# base.net
KiCad netlist of a schematic drawn in EAGLE
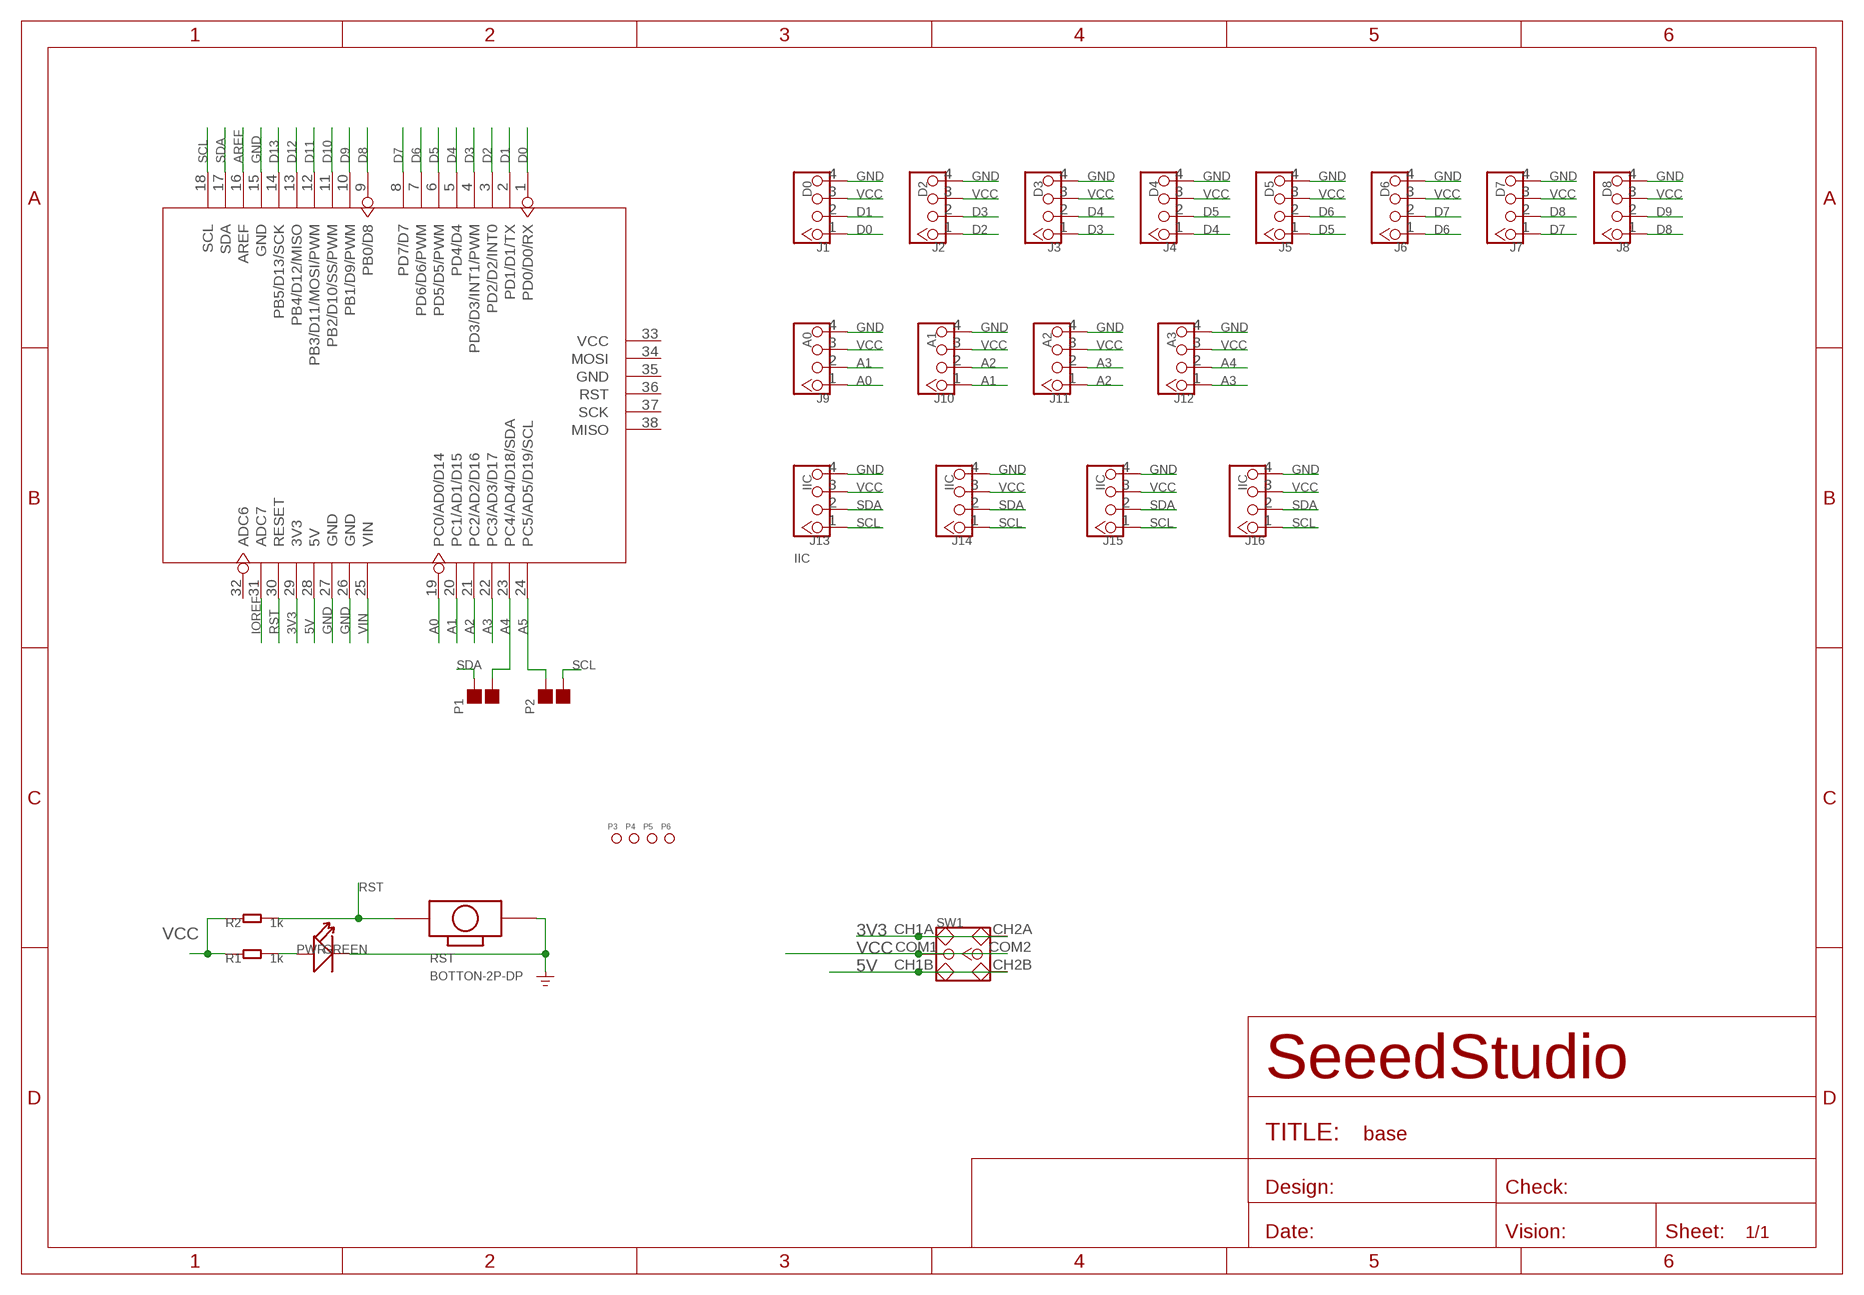
[diagram p0: schematic, sheet 1]

(export (version "E")
  (design (tool "Eeschema 10.0.6"))
  (components
    (comp (ref "J1")
      (value "D0")
      (footprint "eagle-import:4P-2.0")
      (libsource (lib "eagle-import") (part "TWIG-4P-2.0-2.0"))
    )
    (comp (ref "J2")
      (value "D2")
      (footprint "eagle-import:4P-2.0")
      (libsource (lib "eagle-import") (part "TWIG-4P-2.0-2.0"))
    )
    (comp (ref "J3")
      (value "D3")
      (footprint "eagle-import:4P-2.0")
      (libsource (lib "eagle-import") (part "TWIG-4P-2.0-2.0"))
    )
    (comp (ref "J4")
      (value "D4")
      (footprint "eagle-import:4P-2.0")
      (libsource (lib "eagle-import") (part "TWIG-4P-2.0-2.0"))
    )
    (comp (ref "J5")
      (value "D5")
      (footprint "eagle-import:4P-2.0")
      (libsource (lib "eagle-import") (part "TWIG-4P-2.0-2.0"))
    )
    (comp (ref "J6")
      (value "D6")
      (footprint "eagle-import:4P-2.0")
      (libsource (lib "eagle-import") (part "TWIG-4P-2.0-2.0"))
    )
    (comp (ref "J7")
      (value "D7")
      (footprint "eagle-import:4P-2.0")
      (libsource (lib "eagle-import") (part "TWIG-4P-2.0-2.0"))
    )
    (comp (ref "J8")
      (value "D8")
      (footprint "eagle-import:4P-2.0")
      (libsource (lib "eagle-import") (part "TWIG-4P-2.0-2.0"))
    )
    (comp (ref "J9")
      (value "A0")
      (footprint "eagle-import:4P-2.0-90D")
      (libsource (lib "eagle-import") (part "TWIG-4P-2.0'90D'"))
    )
    (comp (ref "J10")
      (value "A1")
      (footprint "eagle-import:4P-2.0-90D")
      (libsource (lib "eagle-import") (part "TWIG-4P-2.0'90D'"))
    )
    (comp (ref "J11")
      (value "A2")
      (footprint "eagle-import:4P-2.0-90D")
      (libsource (lib "eagle-import") (part "TWIG-4P-2.0'90D'"))
    )
    (comp (ref "J12")
      (value "A3")
      (footprint "eagle-import:4P-2.0-90D")
      (libsource (lib "eagle-import") (part "TWIG-4P-2.0'90D'"))
    )
    (comp (ref "J13")
      (value "IIC")
      (footprint "eagle-import:4P-2.0")
      (libsource (lib "eagle-import") (part "TWIG-4P-2.0-2.0"))
    )
    (comp (ref "J14")
      (value "IIC")
      (footprint "eagle-import:4P-2.0")
      (libsource (lib "eagle-import") (part "TWIG-4P-2.0-2.0"))
    )
    (comp (ref "J15")
      (value "IIC")
      (footprint "eagle-import:4P-2.0")
      (libsource (lib "eagle-import") (part "TWIG-4P-2.0-2.0"))
    )
    (comp (ref "J16")
      (value "IIC")
      (footprint "eagle-import:4P-2.0")
      (libsource (lib "eagle-import") (part "TWIG-4P-2.0-2.0"))
    )
    (comp (ref "P1")
      (value "DNP")
      (footprint "eagle-import:2P-SMD-1.78X1.27")
      (libsource (lib "eagle-import") (part "PAD-JUMPER-2P"))
    )
    (comp (ref "P2")
      (value "DNP")
      (footprint "eagle-import:2P-SMD-1.78X1.27")
      (libsource (lib "eagle-import") (part "PAD-JUMPER-2P"))
    )
    (comp (ref "P3")
      (value "PAD-MARK")
      (footprint "eagle-import:ROUND-MARK-1.0")
      (fields (field (name "PARTNO") "DNP"))
      (libsource (lib "eagle-import") (part "PAD-MARK"))
    )
    (comp (ref "P4")
      (value "PAD-MARK")
      (footprint "eagle-import:ROUND-MARK-1.0")
      (fields (field (name "PARTNO") "DNP"))
      (libsource (lib "eagle-import") (part "PAD-MARK"))
    )
    (comp (ref "P5")
      (value "PAD-MARK")
      (footprint "eagle-import:ROUND-MARK-1.0")
      (fields (field (name "PARTNO") "DNP"))
      (libsource (lib "eagle-import") (part "PAD-MARK"))
    )
    (comp (ref "P6")
      (value "PAD-MARK")
      (footprint "eagle-import:ROUND-MARK-1.0")
      (fields (field (name "PARTNO") "DNP"))
      (libsource (lib "eagle-import") (part "PAD-MARK"))
    )
    (comp (ref "PWR")
      (value "GREEN")
      (footprint "eagle-import:LED-2P-2.54-3MM")
      (libsource (lib "eagle-import") (part "LED-3MM"))
    )
    (comp (ref "R1")
      (value "1k")
      (footprint "eagle-import:R0603")
      (libsource (lib "eagle-import") (part "R-0603"))
    )
    (comp (ref "R2")
      (value "1k")
      (footprint "eagle-import:R0603")
      (libsource (lib "eagle-import") (part "R-0603"))
    )
    (comp (ref "RST")
      (value "BOTTON-2P-DP")
      (footprint "eagle-import:2P-7.62X3.56-90D")
      (libsource (lib "eagle-import") (part "BOTTON-2P-90"))
    )
    (comp (ref "SW1")
      (value "SWITCH-2CH-6P'90D'")
      (footprint "eagle-import:6P-2CH-2.5-9.1X3.5X3.2H-90D")
      (libsource (lib "eagle-import") (part "SWITCH-2CH-6P'90D'"))
    )
    (comp (ref "U2")
      (value "DIP Long Blue Female Header")
      (footprint "eagle-import:ARDUINO-38P")
      (libsource (lib "eagle-import") (part "ARDUINO-38P"))
    )
  )
  (nets
    (net (code "1") (name "/3V3") (class "Default")
      (node (ref "SW1") (pin "CH1A") (pinfunction "CH1A_CH1A") (pintype "bidirectional"))
      (node (ref "SW1") (pin "CH2A") (pinfunction "CH2A_CH2A") (pintype "bidirectional"))
      (node (ref "U2") (pin "29") (pinfunction "3V3_29") (pintype "bidirectional"))
    )
    (net (code "2") (name "/5V") (class "Default")
      (node (ref "SW1") (pin "CH1B") (pinfunction "CH1B_CH1B") (pintype "bidirectional"))
      (node (ref "SW1") (pin "CH2B") (pinfunction "CH2B_CH2B") (pintype "bidirectional"))
      (node (ref "U2") (pin "28") (pinfunction "5V_28") (pintype "bidirectional"))
    )
    (net (code "3") (name "/A0") (class "Default")
      (node (ref "J9") (pin "1") (pinfunction "1_1") (pintype "bidirectional"))
      (node (ref "U2") (pin "19") (pinfunction "PC0/AD0/D14_19") (pintype "bidirectional"))
    )
    (net (code "4") (name "/A1") (class "Default")
      (node (ref "J10") (pin "1") (pinfunction "1_1") (pintype "bidirectional"))
      (node (ref "J9") (pin "2") (pinfunction "2_2") (pintype "bidirectional"))
      (node (ref "U2") (pin "20") (pinfunction "PC1/AD1/D15_20") (pintype "bidirectional"))
    )
    (net (code "5") (name "/A2") (class "Default")
      (node (ref "J10") (pin "2") (pinfunction "2_2") (pintype "bidirectional"))
      (node (ref "J11") (pin "1") (pinfunction "1_1") (pintype "bidirectional"))
      (node (ref "U2") (pin "21") (pinfunction "PC2/AD2/D16_21") (pintype "bidirectional"))
    )
    (net (code "6") (name "/A3") (class "Default")
      (node (ref "J11") (pin "2") (pinfunction "2_2") (pintype "bidirectional"))
      (node (ref "J12") (pin "1") (pinfunction "1_1") (pintype "bidirectional"))
      (node (ref "U2") (pin "22") (pinfunction "PC3/AD3/D17_22") (pintype "bidirectional"))
    )
    (net (code "7") (name "/A4") (class "Default")
      (node (ref "J12") (pin "2") (pinfunction "2_2") (pintype "bidirectional"))
      (node (ref "P1") (pin "1") (pinfunction "1_1") (pintype "bidirectional"))
      (node (ref "U2") (pin "23") (pinfunction "PC4/AD4/D18/SDA_23") (pintype "bidirectional"))
    )
    (net (code "8") (name "/A5") (class "Default")
      (node (ref "P2") (pin "2") (pinfunction "2_2") (pintype "bidirectional"))
      (node (ref "U2") (pin "24") (pinfunction "PC5/AD5/D19/SCL_24") (pintype "bidirectional"))
    )
    (net (code "9") (name "/AREF") (class "Default")
      (node (ref "U2") (pin "16") (pinfunction "AREF_16") (pintype "bidirectional"))
    )
    (net (code "10") (name "/D0") (class "Default")
      (node (ref "J1") (pin "1") (pinfunction "1_1") (pintype "bidirectional"))
      (node (ref "U2") (pin "1") (pinfunction "PD0/D0/RX_1") (pintype "bidirectional"))
    )
    (net (code "11") (name "/D1") (class "Default")
      (node (ref "J1") (pin "2") (pinfunction "2_2") (pintype "bidirectional"))
      (node (ref "U2") (pin "2") (pinfunction "PD1/D1/TX_2") (pintype "bidirectional"))
    )
    (net (code "12") (name "/D2") (class "Default")
      (node (ref "J2") (pin "1") (pinfunction "1_1") (pintype "bidirectional"))
      (node (ref "U2") (pin "3") (pinfunction "PD2/D2/INT0_3") (pintype "bidirectional"))
    )
    (net (code "13") (name "/D3") (class "Default")
      (node (ref "J2") (pin "2") (pinfunction "2_2") (pintype "bidirectional"))
      (node (ref "J3") (pin "1") (pinfunction "1_1") (pintype "bidirectional"))
      (node (ref "U2") (pin "4") (pinfunction "PD3/D3/INT1/PWM_4") (pintype "bidirectional"))
    )
    (net (code "14") (name "/D4") (class "Default")
      (node (ref "J3") (pin "2") (pinfunction "2_2") (pintype "bidirectional"))
      (node (ref "J4") (pin "1") (pinfunction "1_1") (pintype "bidirectional"))
      (node (ref "U2") (pin "5") (pinfunction "PD4/D4_5") (pintype "bidirectional"))
    )
    (net (code "15") (name "/D5") (class "Default")
      (node (ref "J4") (pin "2") (pinfunction "2_2") (pintype "bidirectional"))
      (node (ref "J5") (pin "1") (pinfunction "1_1") (pintype "bidirectional"))
      (node (ref "U2") (pin "6") (pinfunction "PD5/D5/PWM_6") (pintype "bidirectional"))
    )
    (net (code "16") (name "/D6") (class "Default")
      (node (ref "J5") (pin "2") (pinfunction "2_2") (pintype "bidirectional"))
      (node (ref "J6") (pin "1") (pinfunction "1_1") (pintype "bidirectional"))
      (node (ref "U2") (pin "7") (pinfunction "PD6/D6/PWM_7") (pintype "bidirectional"))
    )
    (net (code "17") (name "/D7") (class "Default")
      (node (ref "J6") (pin "2") (pinfunction "2_2") (pintype "bidirectional"))
      (node (ref "J7") (pin "1") (pinfunction "1_1") (pintype "bidirectional"))
      (node (ref "U2") (pin "8") (pinfunction "PD7/D7_8") (pintype "bidirectional"))
    )
    (net (code "18") (name "/D8") (class "Default")
      (node (ref "J7") (pin "2") (pinfunction "2_2") (pintype "bidirectional"))
      (node (ref "J8") (pin "1") (pinfunction "1_1") (pintype "bidirectional"))
      (node (ref "U2") (pin "9") (pinfunction "PB0/D8_9") (pintype "bidirectional"))
    )
    (net (code "19") (name "/D9") (class "Default")
      (node (ref "J8") (pin "2") (pinfunction "2_2") (pintype "bidirectional"))
      (node (ref "U2") (pin "10") (pinfunction "PB1/D9/PWM_10") (pintype "bidirectional"))
    )
    (net (code "20") (name "/D10") (class "Default")
      (node (ref "U2") (pin "11") (pinfunction "PB2/D10/SS/PWM_11") (pintype "bidirectional"))
    )
    (net (code "21") (name "/D11") (class "Default")
      (node (ref "U2") (pin "12") (pinfunction "PB3/D11/MOSI/PWM_12") (pintype "bidirectional"))
    )
    (net (code "22") (name "/D12") (class "Default")
      (node (ref "U2") (pin "13") (pinfunction "PB4/D12/MISO_13") (pintype "bidirectional"))
    )
    (net (code "23") (name "/D13") (class "Default")
      (node (ref "U2") (pin "14") (pinfunction "PB5/D13/SCK_14") (pintype "bidirectional"))
    )
    (net (code "24") (name "/IOREF") (class "Default")
      (node (ref "U2") (pin "31") (pinfunction "ADC7_31") (pintype "bidirectional"))
    )
    (net (code "25") (name "/RST") (class "Default")
      (node (ref "R2") (pin "2") (pinfunction "2_2") (pintype "passive"))
      (node (ref "RST") (pin "P$1") (pinfunction "1_P$1") (pintype "bidirectional"))
      (node (ref "U2") (pin "30") (pinfunction "RESET_30") (pintype "bidirectional"))
    )
    (net (code "26") (name "/SCL") (class "Default")
      (node (ref "J13") (pin "1") (pinfunction "1_1") (pintype "bidirectional"))
      (node (ref "J14") (pin "1") (pinfunction "1_1") (pintype "bidirectional"))
      (node (ref "J15") (pin "1") (pinfunction "1_1") (pintype "bidirectional"))
      (node (ref "J16") (pin "1") (pinfunction "1_1") (pintype "bidirectional"))
      (node (ref "P2") (pin "1") (pinfunction "1_1") (pintype "bidirectional"))
      (node (ref "U2") (pin "18") (pinfunction "SCL_18") (pintype "bidirectional"))
    )
    (net (code "27") (name "/SDA") (class "Default")
      (node (ref "J13") (pin "2") (pinfunction "2_2") (pintype "bidirectional"))
      (node (ref "J14") (pin "2") (pinfunction "2_2") (pintype "bidirectional"))
      (node (ref "J15") (pin "2") (pinfunction "2_2") (pintype "bidirectional"))
      (node (ref "J16") (pin "2") (pinfunction "2_2") (pintype "bidirectional"))
      (node (ref "P1") (pin "2") (pinfunction "2_2") (pintype "bidirectional"))
      (node (ref "U2") (pin "17") (pinfunction "SDA_17") (pintype "bidirectional"))
    )
    (net (code "28") (name "/VCC") (class "Default")
      (node (ref "J1") (pin "3") (pinfunction "3_3") (pintype "bidirectional"))
      (node (ref "J10") (pin "3") (pinfunction "3_3") (pintype "bidirectional"))
      (node (ref "J11") (pin "3") (pinfunction "3_3") (pintype "bidirectional"))
      (node (ref "J12") (pin "3") (pinfunction "3_3") (pintype "bidirectional"))
      (node (ref "J13") (pin "3") (pinfunction "3_3") (pintype "bidirectional"))
      (node (ref "J14") (pin "3") (pinfunction "3_3") (pintype "bidirectional"))
      (node (ref "J15") (pin "3") (pinfunction "3_3") (pintype "bidirectional"))
      (node (ref "J16") (pin "3") (pinfunction "3_3") (pintype "bidirectional"))
      (node (ref "J2") (pin "3") (pinfunction "3_3") (pintype "bidirectional"))
      (node (ref "J3") (pin "3") (pinfunction "3_3") (pintype "bidirectional"))
      (node (ref "J4") (pin "3") (pinfunction "3_3") (pintype "bidirectional"))
      (node (ref "J5") (pin "3") (pinfunction "3_3") (pintype "bidirectional"))
      (node (ref "J6") (pin "3") (pinfunction "3_3") (pintype "bidirectional"))
      (node (ref "J7") (pin "3") (pinfunction "3_3") (pintype "bidirectional"))
      (node (ref "J8") (pin "3") (pinfunction "3_3") (pintype "bidirectional"))
      (node (ref "J9") (pin "3") (pinfunction "3_3") (pintype "bidirectional"))
      (node (ref "R1") (pin "1") (pinfunction "1_1") (pintype "passive"))
      (node (ref "R2") (pin "1") (pinfunction "1_1") (pintype "passive"))
      (node (ref "SW1") (pin "COM1") (pinfunction "COM1_COM1") (pintype "bidirectional"))
      (node (ref "SW1") (pin "COM2") (pinfunction "COM2_COM2") (pintype "bidirectional"))
    )
    (net (code "29") (name "/VIN") (class "Default")
      (node (ref "U2") (pin "25") (pinfunction "VIN_25") (pintype "bidirectional"))
    )
    (net (code "30") (name "GND_POWER") (class "Default")
      (node (ref "J1") (pin "4") (pinfunction "4_4") (pintype "bidirectional"))
      (node (ref "J10") (pin "4") (pinfunction "4_4") (pintype "bidirectional"))
      (node (ref "J11") (pin "4") (pinfunction "4_4") (pintype "bidirectional"))
      (node (ref "J12") (pin "4") (pinfunction "4_4") (pintype "bidirectional"))
      (node (ref "J13") (pin "4") (pinfunction "4_4") (pintype "bidirectional"))
      (node (ref "J14") (pin "4") (pinfunction "4_4") (pintype "bidirectional"))
      (node (ref "J15") (pin "4") (pinfunction "4_4") (pintype "bidirectional"))
      (node (ref "J16") (pin "4") (pinfunction "4_4") (pintype "bidirectional"))
      (node (ref "J2") (pin "4") (pinfunction "4_4") (pintype "bidirectional"))
      (node (ref "J3") (pin "4") (pinfunction "4_4") (pintype "bidirectional"))
      (node (ref "J4") (pin "4") (pinfunction "4_4") (pintype "bidirectional"))
      (node (ref "J5") (pin "4") (pinfunction "4_4") (pintype "bidirectional"))
      (node (ref "J6") (pin "4") (pinfunction "4_4") (pintype "bidirectional"))
      (node (ref "J7") (pin "4") (pinfunction "4_4") (pintype "bidirectional"))
      (node (ref "J8") (pin "4") (pinfunction "4_4") (pintype "bidirectional"))
      (node (ref "J9") (pin "4") (pinfunction "4_4") (pintype "bidirectional"))
      (node (ref "PWR") (pin "K") (pinfunction "-_K") (pintype "passive"))
      (node (ref "RST") (pin "P$2") (pinfunction "2_P$2") (pintype "bidirectional"))
      (node (ref "U2") (pin "15") (pinfunction "GND_15") (pintype "bidirectional"))
      (node (ref "U2") (pin "26") (pinfunction "GND_26") (pintype "bidirectional"))
      (node (ref "U2") (pin "27") (pinfunction "GND_27") (pintype "bidirectional"))
    )
    (net (code "31") (name "Net-(PWR-+)") (class "Default")
      (node (ref "PWR") (pin "A") (pinfunction "+_A") (pintype "passive"))
      (node (ref "R1") (pin "2") (pinfunction "2_2") (pintype "passive"))
    )
    (net (code "32") (name "unconnected-(U2-ADC6-Pad32)") (class "Default")
      (node (ref "U2") (pin "32") (pinfunction "ADC6_32") (pintype "bidirectional"))
    )
    (net (code "33") (name "unconnected-(U2-GND-Pad35)") (class "Default")
      (node (ref "U2") (pin "35") (pinfunction "GND_35") (pintype "bidirectional"))
    )
    (net (code "34") (name "unconnected-(U2-MISO-Pad38)") (class "Default")
      (node (ref "U2") (pin "38") (pinfunction "MISO_38") (pintype "bidirectional"))
    )
    (net (code "35") (name "unconnected-(U2-MOSI-Pad34)") (class "Default")
      (node (ref "U2") (pin "34") (pinfunction "MOSI_34") (pintype "bidirectional"))
    )
    (net (code "36") (name "unconnected-(U2-RST-Pad36)") (class "Default")
      (node (ref "U2") (pin "36") (pinfunction "RST_36") (pintype "bidirectional"))
    )
    (net (code "37") (name "unconnected-(U2-SCK-Pad37)") (class "Default")
      (node (ref "U2") (pin "37") (pinfunction "SCK_37") (pintype "bidirectional"))
    )
    (net (code "38") (name "unconnected-(U2-VCC-Pad33)") (class "Default")
      (node (ref "U2") (pin "33") (pinfunction "VCC_33") (pintype "bidirectional"))
    )
  )
)
